# Nusbio_2_-_IC2_Extension.net
KiCad netlist of a schematic drawn in EAGLE
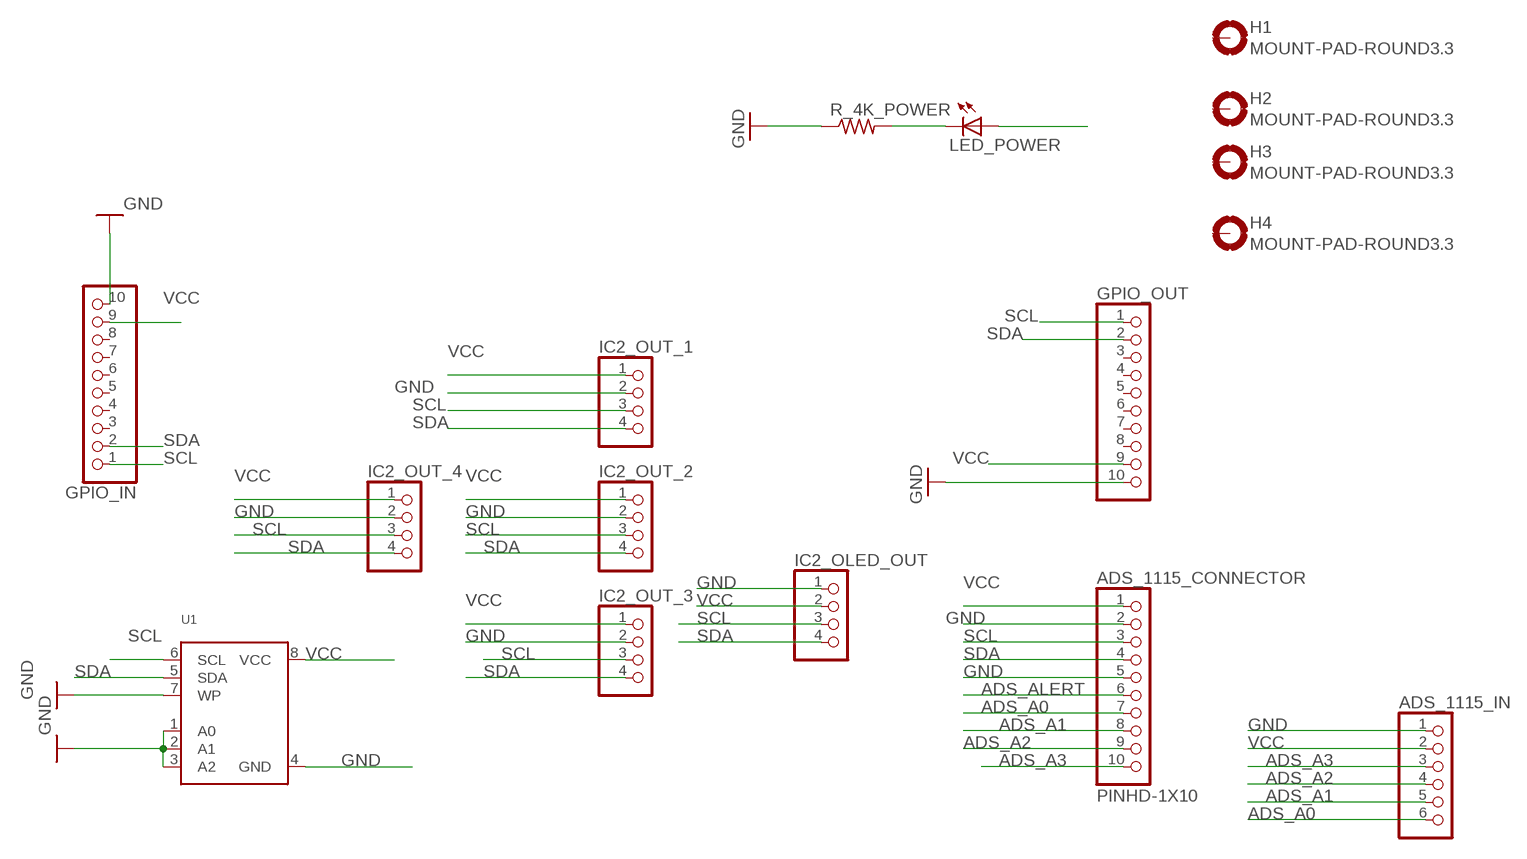
[diagram p0: schematic, sheet 1]

(export (version "E")
  (design (tool "Eeschema 10.0.6"))
  (components
    (comp (ref "ADS_1115_CONNECTOR")
      (value "PINHD-1X10")
      (footprint "eagle-import:1X10-BIG")
      (libsource (lib "eagle-import") (part "PINHD-1X10"))
    )
    (comp (ref "ADS_1115_IN")
      (value "PINHD-1X6")
      (footprint "eagle-import:1X06")
      (libsource (lib "eagle-import") (part "PINHD-1X6"))
    )
    (comp (ref "GPIO_IN")
      (value "PINHD-1X10")
      (footprint "eagle-import:1X10-BIG")
      (libsource (lib "eagle-import") (part "PINHD-1X10"))
    )
    (comp (ref "GPIO_OUT")
      (value "PINHD-1X10")
      (footprint "eagle-import:1X10-BIG")
      (libsource (lib "eagle-import") (part "PINHD-1X10"))
    )
    (comp (ref "H1")
      (value "MOUNT-PAD-ROUND3.3")
      (footprint "eagle-import:3,3-PAD")
      (libsource (lib "eagle-import") (part "MOUNT-PAD-ROUND3.3"))
    )
    (comp (ref "H2")
      (value "MOUNT-PAD-ROUND3.3")
      (footprint "eagle-import:3,3-PAD")
      (libsource (lib "eagle-import") (part "MOUNT-PAD-ROUND3.3"))
    )
    (comp (ref "H3")
      (value "MOUNT-PAD-ROUND3.3")
      (footprint "eagle-import:3,3-PAD")
      (libsource (lib "eagle-import") (part "MOUNT-PAD-ROUND3.3"))
    )
    (comp (ref "H4")
      (value "MOUNT-PAD-ROUND3.3")
      (footprint "eagle-import:3,3-PAD")
      (libsource (lib "eagle-import") (part "MOUNT-PAD-ROUND3.3"))
    )
    (comp (ref "IC2_OLED_OUT")
      (value "PINHD-1X4")
      (footprint "eagle-import:1X04")
      (libsource (lib "eagle-import") (part "PINHD-1X4"))
    )
    (comp (ref "IC2_OUT_1")
      (value "PINHD-1X4")
      (footprint "eagle-import:1X04")
      (libsource (lib "eagle-import") (part "PINHD-1X4"))
    )
    (comp (ref "IC2_OUT_2")
      (value "PINHD-1X4")
      (footprint "eagle-import:1X04")
      (libsource (lib "eagle-import") (part "PINHD-1X4"))
    )
    (comp (ref "IC2_OUT_3")
      (value "PINHD-1X4")
      (footprint "eagle-import:1X04")
      (libsource (lib "eagle-import") (part "PINHD-1X4"))
    )
    (comp (ref "IC2_OUT_4")
      (value "PINHD-1X4")
      (footprint "eagle-import:1X04")
      (libsource (lib "eagle-import") (part "PINHD-1X4"))
    )
    (comp (ref "LED_POWER")
      (value "LEDSMT1206")
      (footprint "eagle-import:1206")
      (libsource (lib "eagle-import") (part "LEDSMT1206"))
    )
    (comp (ref "R_4K_POWER")
      (value "R-US_R1206")
      (footprint "eagle-import:R1206")
      (libsource (lib "eagle-import") (part "R-US_R1206"))
    )
    (comp (ref "U1")
      (value "EEPROM_I2C_SOIC8_GENERIC")
      (footprint "eagle-import:SOIC8_150MIL")
      (libsource (lib "eagle-import") (part "EEPROM_I2C_SOIC8_GENERIC"))
    )
  )
  (nets
    (net (code "1") (name "/ADS_A0") (class "Default")
      (node (ref "ADS_1115_CONNECTOR") (pin "7") (pinfunction "7_7") (pintype "passive"))
      (node (ref "ADS_1115_IN") (pin "6") (pinfunction "6_6") (pintype "passive"))
    )
    (net (code "2") (name "/ADS_A1") (class "Default")
      (node (ref "ADS_1115_CONNECTOR") (pin "8") (pinfunction "8_8") (pintype "passive"))
      (node (ref "ADS_1115_IN") (pin "5") (pinfunction "5_5") (pintype "passive"))
    )
    (net (code "3") (name "/ADS_A2") (class "Default")
      (node (ref "ADS_1115_CONNECTOR") (pin "9") (pinfunction "9_9") (pintype "passive"))
      (node (ref "ADS_1115_IN") (pin "4") (pinfunction "4_4") (pintype "passive"))
    )
    (net (code "4") (name "/ADS_A3") (class "Default")
      (node (ref "ADS_1115_CONNECTOR") (pin "10") (pinfunction "10_10") (pintype "passive"))
      (node (ref "ADS_1115_IN") (pin "3") (pinfunction "3_3") (pintype "passive"))
    )
    (net (code "5") (name "/ADS_ALERT") (class "Default")
      (node (ref "ADS_1115_CONNECTOR") (pin "6") (pinfunction "6_6") (pintype "passive"))
    )
    (net (code "6") (name "/SCL") (class "Default")
      (node (ref "ADS_1115_CONNECTOR") (pin "3") (pinfunction "3_3") (pintype "passive"))
      (node (ref "GPIO_IN") (pin "1") (pinfunction "1_1") (pintype "passive"))
      (node (ref "GPIO_OUT") (pin "1") (pinfunction "1_1") (pintype "passive"))
      (node (ref "IC2_OLED_OUT") (pin "3") (pinfunction "3_3") (pintype "passive"))
      (node (ref "IC2_OUT_1") (pin "3") (pinfunction "3_3") (pintype "passive"))
      (node (ref "IC2_OUT_2") (pin "3") (pinfunction "3_3") (pintype "passive"))
      (node (ref "IC2_OUT_3") (pin "3") (pinfunction "3_3") (pintype "passive"))
      (node (ref "IC2_OUT_4") (pin "3") (pinfunction "3_3") (pintype "passive"))
      (node (ref "U1") (pin "6") (pinfunction "SCL_6") (pintype "input"))
    )
    (net (code "7") (name "/SDA") (class "Default")
      (node (ref "ADS_1115_CONNECTOR") (pin "4") (pinfunction "4_4") (pintype "passive"))
      (node (ref "GPIO_IN") (pin "2") (pinfunction "2_2") (pintype "passive"))
      (node (ref "GPIO_OUT") (pin "2") (pinfunction "2_2") (pintype "passive"))
      (node (ref "IC2_OLED_OUT") (pin "4") (pinfunction "4_4") (pintype "passive"))
      (node (ref "IC2_OUT_1") (pin "4") (pinfunction "4_4") (pintype "passive"))
      (node (ref "IC2_OUT_2") (pin "4") (pinfunction "4_4") (pintype "passive"))
      (node (ref "IC2_OUT_3") (pin "4") (pinfunction "4_4") (pintype "passive"))
      (node (ref "IC2_OUT_4") (pin "4") (pinfunction "4_4") (pintype "passive"))
      (node (ref "U1") (pin "5") (pinfunction "SDA_5") (pintype "bidirectional"))
    )
    (net (code "8") (name "/VCC") (class "Default")
      (node (ref "ADS_1115_CONNECTOR") (pin "1") (pinfunction "1_1") (pintype "passive"))
      (node (ref "ADS_1115_IN") (pin "2") (pinfunction "2_2") (pintype "passive"))
      (node (ref "GPIO_IN") (pin "9") (pinfunction "9_9") (pintype "passive"))
      (node (ref "GPIO_OUT") (pin "9") (pinfunction "9_9") (pintype "passive"))
      (node (ref "IC2_OLED_OUT") (pin "2") (pinfunction "2_2") (pintype "passive"))
      (node (ref "IC2_OUT_1") (pin "1") (pinfunction "1_1") (pintype "passive"))
      (node (ref "IC2_OUT_2") (pin "1") (pinfunction "1_1") (pintype "passive"))
      (node (ref "IC2_OUT_3") (pin "1") (pinfunction "1_1") (pintype "passive"))
      (node (ref "IC2_OUT_4") (pin "1") (pinfunction "1_1") (pintype "passive"))
      (node (ref "LED_POWER") (pin "A") (pinfunction "A_A") (pintype "passive"))
      (node (ref "U1") (pin "8") (pinfunction "VCC_8") (pintype "power_in"))
    )
    (net (code "9") (name "GND") (class "Default")
      (node (ref "ADS_1115_CONNECTOR") (pin "2") (pinfunction "2_2") (pintype "passive"))
      (node (ref "ADS_1115_CONNECTOR") (pin "5") (pinfunction "5_5") (pintype "passive"))
      (node (ref "ADS_1115_IN") (pin "1") (pinfunction "1_1") (pintype "passive"))
      (node (ref "GPIO_IN") (pin "10") (pinfunction "10_10") (pintype "passive"))
      (node (ref "GPIO_OUT") (pin "10") (pinfunction "10_10") (pintype "passive"))
      (node (ref "IC2_OLED_OUT") (pin "1") (pinfunction "1_1") (pintype "passive"))
      (node (ref "IC2_OUT_1") (pin "2") (pinfunction "2_2") (pintype "passive"))
      (node (ref "IC2_OUT_2") (pin "2") (pinfunction "2_2") (pintype "passive"))
      (node (ref "IC2_OUT_3") (pin "2") (pinfunction "2_2") (pintype "passive"))
      (node (ref "IC2_OUT_4") (pin "2") (pinfunction "2_2") (pintype "passive"))
      (node (ref "R_4K_POWER") (pin "1") (pinfunction "1_1") (pintype "passive"))
      (node (ref "U1") (pin "1") (pinfunction "A0_1") (pintype "input"))
      (node (ref "U1") (pin "2") (pinfunction "A1_2") (pintype "input"))
      (node (ref "U1") (pin "3") (pinfunction "A2_3") (pintype "input"))
      (node (ref "U1") (pin "4") (pinfunction "GND_4") (pintype "power_in"))
      (node (ref "U1") (pin "7") (pinfunction "WP_7") (pintype "input"))
    )
    (net (code "10") (name "Net-(LED_POWER-PadC)") (class "Default")
      (node (ref "LED_POWER") (pin "C") (pinfunction "C_C") (pintype "passive"))
      (node (ref "R_4K_POWER") (pin "2") (pinfunction "2_2") (pintype "passive"))
    )
    (net (code "11") (name "unconnected-(GPIO_IN-Pad3)") (class "Default")
      (node (ref "GPIO_IN") (pin "3") (pinfunction "3_3") (pintype "passive"))
    )
    (net (code "12") (name "unconnected-(GPIO_IN-Pad4)") (class "Default")
      (node (ref "GPIO_IN") (pin "4") (pinfunction "4_4") (pintype "passive"))
    )
    (net (code "13") (name "unconnected-(GPIO_IN-Pad5)") (class "Default")
      (node (ref "GPIO_IN") (pin "5") (pinfunction "5_5") (pintype "passive"))
    )
    (net (code "14") (name "unconnected-(GPIO_IN-Pad6)") (class "Default")
      (node (ref "GPIO_IN") (pin "6") (pinfunction "6_6") (pintype "passive"))
    )
    (net (code "15") (name "unconnected-(GPIO_IN-Pad7)") (class "Default")
      (node (ref "GPIO_IN") (pin "7") (pinfunction "7_7") (pintype "passive"))
    )
    (net (code "16") (name "unconnected-(GPIO_IN-Pad8)") (class "Default")
      (node (ref "GPIO_IN") (pin "8") (pinfunction "8_8") (pintype "passive"))
    )
    (net (code "17") (name "unconnected-(GPIO_OUT-Pad3)") (class "Default")
      (node (ref "GPIO_OUT") (pin "3") (pinfunction "3_3") (pintype "passive"))
    )
    (net (code "18") (name "unconnected-(GPIO_OUT-Pad4)") (class "Default")
      (node (ref "GPIO_OUT") (pin "4") (pinfunction "4_4") (pintype "passive"))
    )
    (net (code "19") (name "unconnected-(GPIO_OUT-Pad5)") (class "Default")
      (node (ref "GPIO_OUT") (pin "5") (pinfunction "5_5") (pintype "passive"))
    )
    (net (code "20") (name "unconnected-(GPIO_OUT-Pad6)") (class "Default")
      (node (ref "GPIO_OUT") (pin "6") (pinfunction "6_6") (pintype "passive"))
    )
    (net (code "21") (name "unconnected-(GPIO_OUT-Pad7)") (class "Default")
      (node (ref "GPIO_OUT") (pin "7") (pinfunction "7_7") (pintype "passive"))
    )
    (net (code "22") (name "unconnected-(GPIO_OUT-Pad8)") (class "Default")
      (node (ref "GPIO_OUT") (pin "8") (pinfunction "8_8") (pintype "passive"))
    )
    (net (code "23") (name "unconnected-(H1-MOUNT-PadB3,3)") (class "Default")
      (node (ref "H1") (pin "B3,3") (pinfunction "MOUNT_B3,3") (pintype "passive"))
    )
    (net (code "24") (name "unconnected-(H2-MOUNT-PadB3,3)") (class "Default")
      (node (ref "H2") (pin "B3,3") (pinfunction "MOUNT_B3,3") (pintype "passive"))
    )
    (net (code "25") (name "unconnected-(H3-MOUNT-PadB3,3)") (class "Default")
      (node (ref "H3") (pin "B3,3") (pinfunction "MOUNT_B3,3") (pintype "passive"))
    )
    (net (code "26") (name "unconnected-(H4-MOUNT-PadB3,3)") (class "Default")
      (node (ref "H4") (pin "B3,3") (pinfunction "MOUNT_B3,3") (pintype "passive"))
    )
  )
)
